# Schematic.net
KiCad netlist of a schematic drawn in EasyEDA
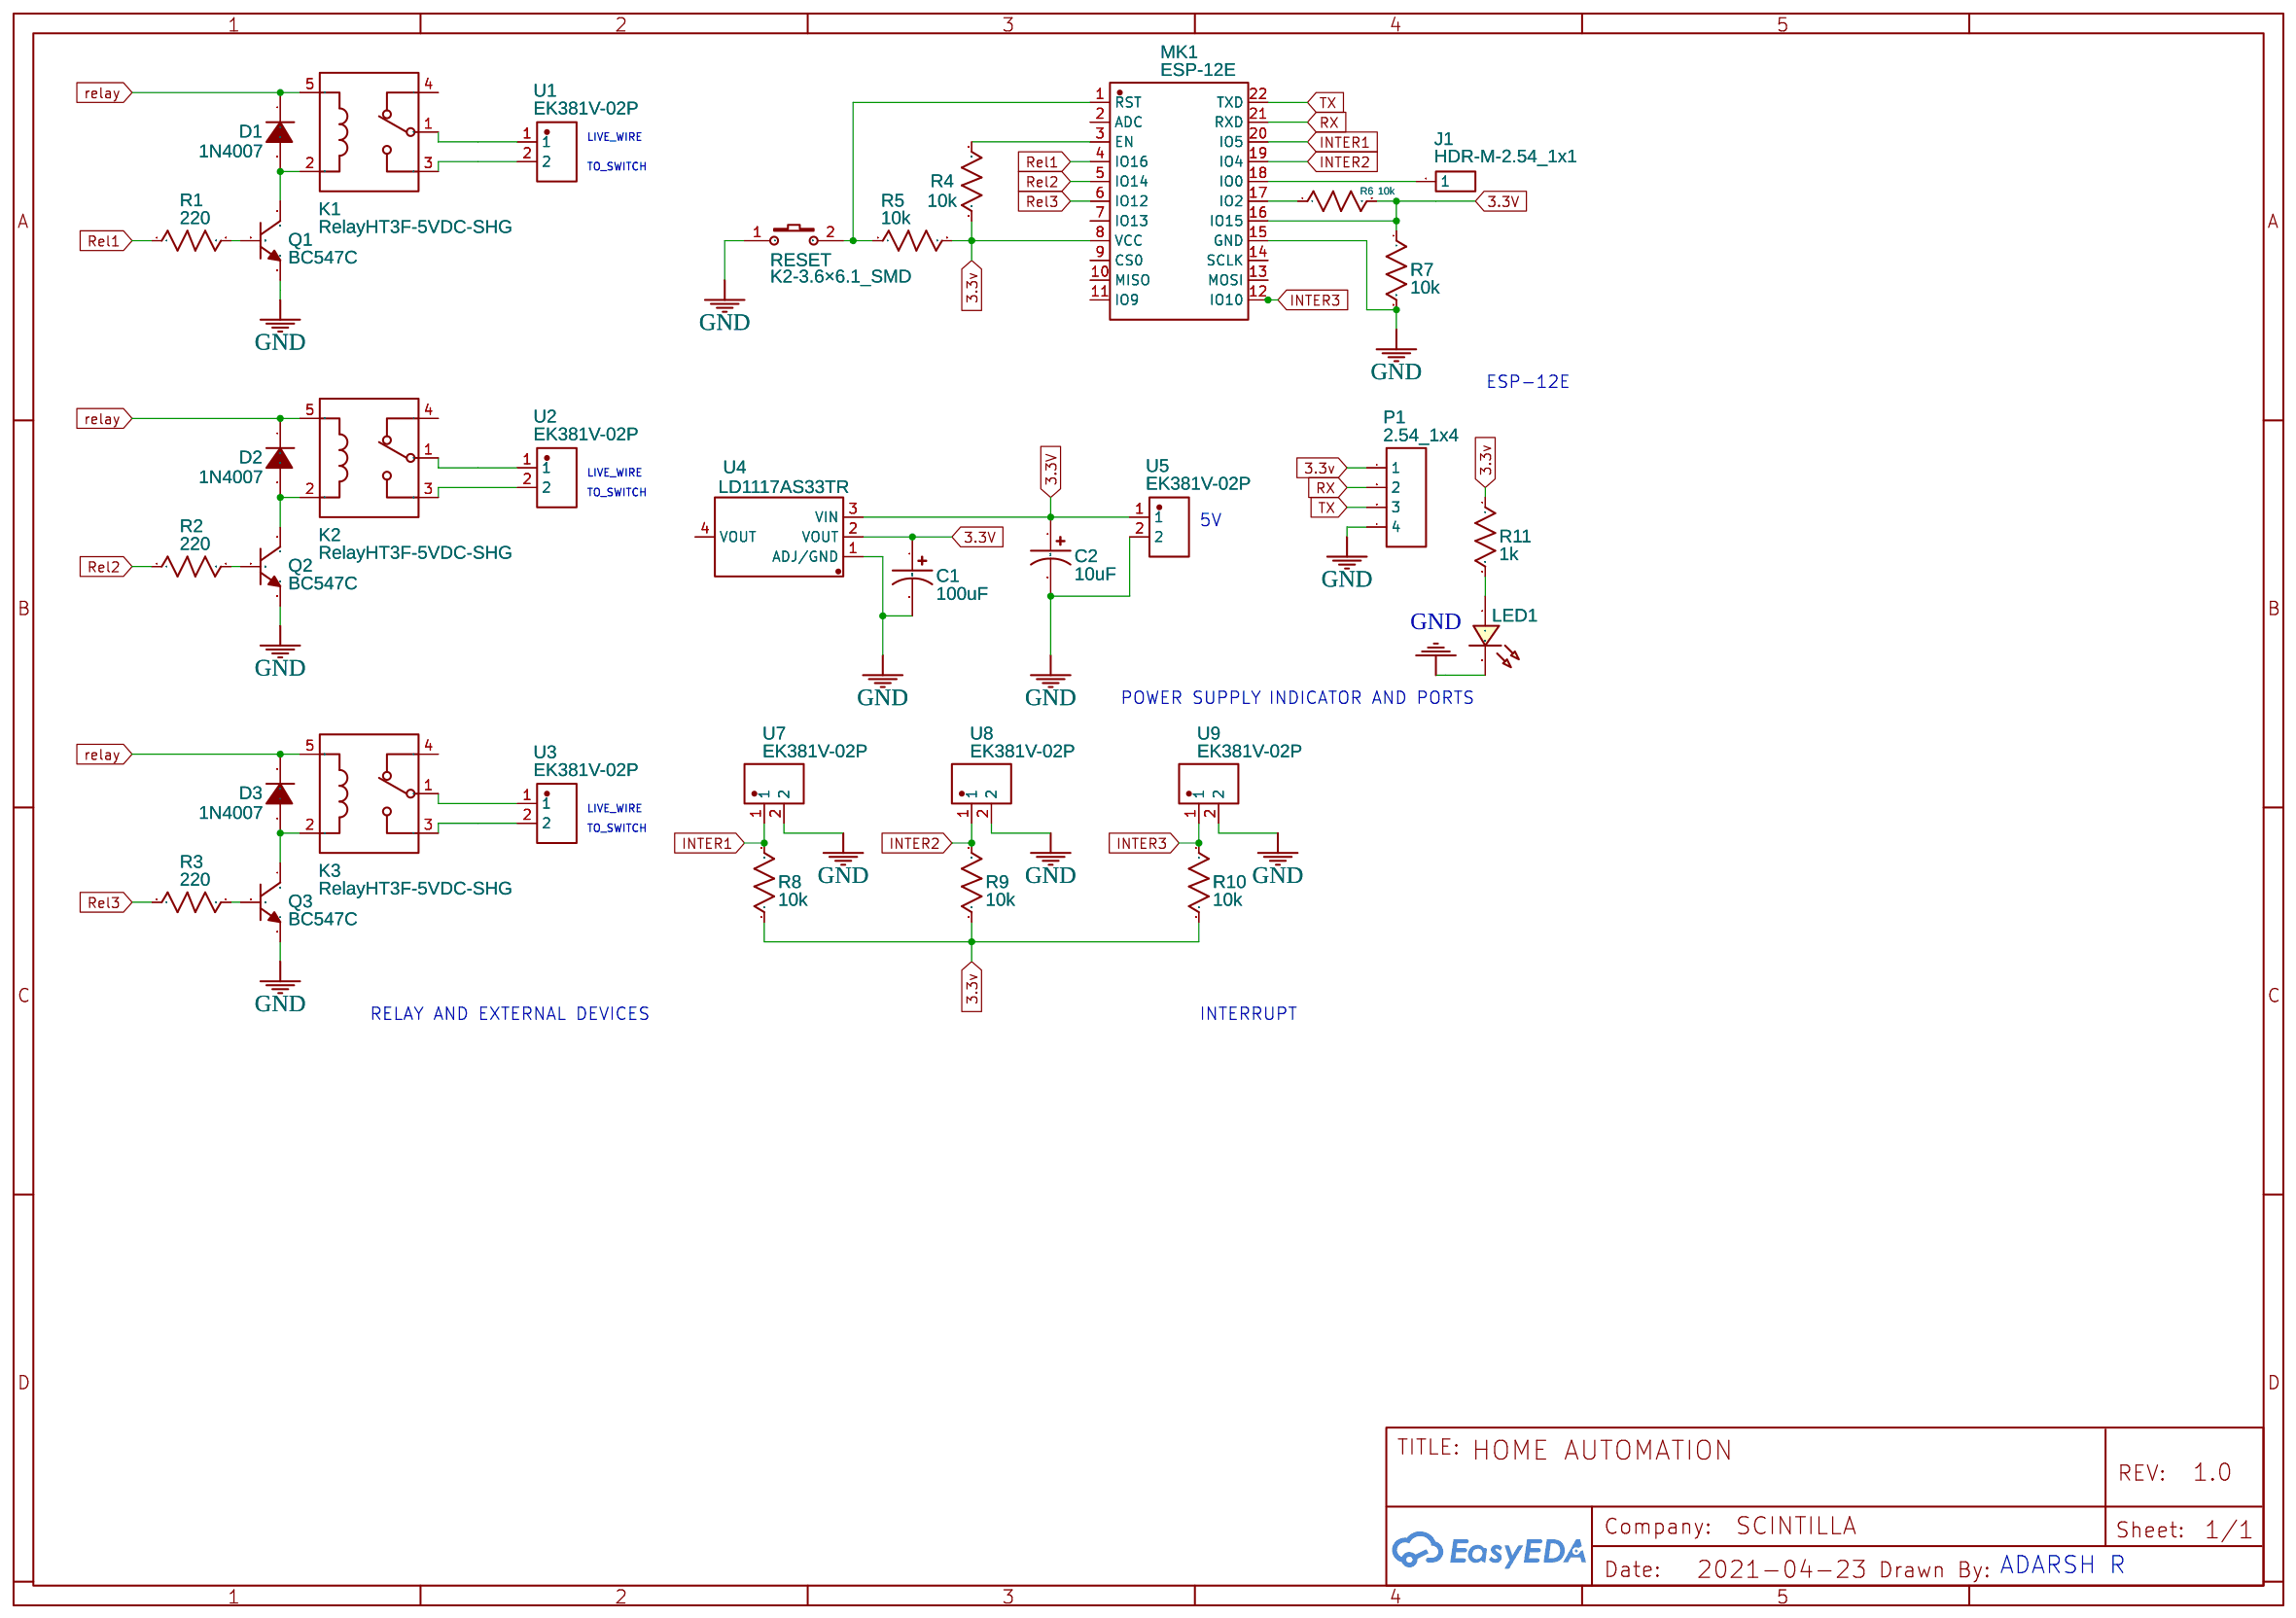
[diagram p0: schematic sheet]

(export (version "E")
  (design (tool "Eeschema 10.0.6"))
  (components
    (comp (ref "C1") (value "100uF") (libsource (lib "") (part "C_Tan_SMD_A_US")))
    (comp (ref "C2") (value "10uF") (libsource (lib "") (part "C_Tan_SMD_A_US")))
    (comp (ref "D1")
      (value "1N4007")
      (fields (field (name "BOM_Supplier Part") "C106903"))
      (libsource (lib "") (part "1N4007"))
    )
    (comp (ref "D2")
      (value "1N4007")
      (fields (field (name "BOM_Supplier Part") "C106903"))
      (libsource (lib "") (part "1N4007"))
    )
    (comp (ref "D3")
      (value "1N4007")
      (fields (field (name "BOM_Supplier Part") "C106903"))
      (libsource (lib "") (part "1N4007"))
    )
    (comp (ref "J1")
      (value "HDR-M-2.54_1x1")
      (fields (field (name "BOM_Supplier Part") "C81276"))
      (libsource (lib "") (part "HDR-M-2.54_1x1"))
    )
    (comp (ref "K1")
      (value "RelayHT3F-5VDC-SHG")
      (fields
        (field (name "BOM_Manufacturer Part") "RelayHT3F-12VDC-SHG")
        (field (name "BOM_Supplier Part") "C22022")
      )
      (libsource (lib "") (part "RelayHT3F-12VDC-SHG"))
    )
    (comp (ref "K2")
      (value "RelayHT3F-5VDC-SHG")
      (fields
        (field (name "BOM_Manufacturer Part") "RelayHT3F-12VDC-SHG")
        (field (name "BOM_Supplier Part") "C22022")
      )
      (libsource (lib "") (part "RelayHT3F-12VDC-SHG"))
    )
    (comp (ref "K3")
      (value "RelayHT3F-5VDC-SHG")
      (fields
        (field (name "BOM_Manufacturer Part") "RelayHT3F-12VDC-SHG")
        (field (name "BOM_Supplier Part") "C22022")
      )
      (libsource (lib "") (part "RelayHT3F-12VDC-SHG"))
    )
    (comp (ref "LED1")
      (value "LED-0603_R")
      (fields
        (field (name "BOM_Manufacturer Part") "19-217/R6C-AL1M2VY/3T")
        (field (name "BOM_Supplier Part") "C72044")
      )
      (libsource (lib "") (part "LED-0603_R"))
    )
    (comp (ref "MK1")
      (value "ESP-12E")
      (fields (field (name "BOM_Supplier Part") "C89297"))
      (libsource (lib "") (part "ESP-12E"))
    )
    (comp (ref "P1")
      (value "2.54_1x4")
      (fields
        (field (name "BOM_Manufacturer Part") "Header-Female-2.54_1x4")
        (field (name "BOM_Supplier Part") "C124413")
      )
      (libsource (lib "") (part "Header-Female-2.54_1x4"))
    )
    (comp (ref "Q1")
      (value "BC547C")
      (fields (field (name "BOM_Supplier Part") "C713614"))
      (libsource (lib "") (part "BC547C"))
    )
    (comp (ref "Q2")
      (value "BC547C")
      (fields (field (name "BOM_Supplier Part") "C713614"))
      (libsource (lib "") (part "BC547C"))
    )
    (comp (ref "Q3")
      (value "BC547C")
      (fields (field (name "BOM_Supplier Part") "C713614"))
      (libsource (lib "") (part "BC547C"))
    )
    (comp (ref "R1") (value "220") (libsource (lib "") (part "R_0603_US_1")))
    (comp (ref "R2") (value "220") (libsource (lib "") (part "R_0603_US_1")))
    (comp (ref "R3") (value "220") (libsource (lib "") (part "R_0603_US_1")))
    (comp (ref "R4") (value "10k") (libsource (lib "") (part "R_0603_US")))
    (comp (ref "R5") (value "10k") (libsource (lib "") (part "R_0603_US_1")))
    (comp (ref "R6") (value "10k") (libsource (lib "") (part "R_0603_US_1")))
    (comp (ref "R7") (value "10k") (libsource (lib "") (part "R_0603_US_2")))
    (comp (ref "R8") (value "10k") (libsource (lib "") (part "R_0603_US")))
    (comp (ref "R9") (value "10k") (libsource (lib "") (part "R_0603_US")))
    (comp (ref "R10") (value "10k") (libsource (lib "") (part "R_0603_US_2")))
    (comp (ref "R11") (value "1k") (libsource (lib "") (part "R_0603_US_2")))
    (comp (ref "RESET")
      (value "K2-3.6×6.1_SMD")
      (fields
        (field (name "BOM_Manufacturer Part") "K2-1107ST-A4SW-06")
        (field (name "BOM_Supplier Part") "C118141")
      )
      (libsource (lib "") (part "K2-3.6×6.1_SMD"))
    )
    (comp (ref "U1")
      (value "EK381V-02P")
      (fields (field (name "BOM_Supplier Part") "C192645"))
      (libsource (lib "") (part "EK381V-02P_1"))
    )
    (comp (ref "U2")
      (value "EK381V-02P")
      (fields (field (name "BOM_Supplier Part") "C192645"))
      (libsource (lib "") (part "EK381V-02P_1"))
    )
    (comp (ref "U3")
      (value "EK381V-02P")
      (fields (field (name "BOM_Supplier Part") "C192645"))
      (libsource (lib "") (part "EK381V-02P_1"))
    )
    (comp (ref "U4")
      (value "LD1117AS33TR")
      (fields (field (name "BOM_Supplier Part") "C115288"))
      (libsource (lib "") (part "LD1117AS33TR"))
    )
    (comp (ref "U5")
      (value "EK381V-02P")
      (fields (field (name "BOM_Supplier Part") "C192645"))
      (libsource (lib "") (part "EK381V-02P_1"))
    )
    (comp (ref "U7")
      (value "EK381V-02P")
      (fields (field (name "BOM_Supplier Part") "C192645"))
      (libsource (lib "") (part "EK381V-02P"))
    )
    (comp (ref "U8")
      (value "EK381V-02P")
      (fields (field (name "BOM_Supplier Part") "C192645"))
      (libsource (lib "") (part "EK381V-02P"))
    )
    (comp (ref "U9")
      (value "EK381V-02P")
      (fields (field (name "BOM_Supplier Part") "C192645"))
      (libsource (lib "") (part "EK381V-02P"))
    )
  )
  (nets
    (net (code "1") (name "3.3V") (class "Default")
      (node (ref "C1") (pin "1") (pinfunction "1_1") (pintype "unspecified"))
      (node (ref "C2") (pin "1") (pinfunction "1_1") (pintype "unspecified"))
      (node (ref "MK1") (pin "16") (pinfunction "IO15_16") (pintype "unspecified"))
      (node (ref "R6") (pin "2") (pinfunction "2_2") (pintype "unspecified"))
      (node (ref "R7") (pin "1") (pinfunction "1_1") (pintype "unspecified"))
      (node (ref "U4") (pin "2") (pinfunction "VOUT_2") (pintype "unspecified"))
      (node (ref "U4") (pin "3") (pinfunction "VIN_3") (pintype "unspecified"))
      (node (ref "U5") (pin "1") (pinfunction "1_1") (pintype "unspecified"))
    )
    (net (code "2") (name "3.3v") (class "Default")
      (node (ref "MK1") (pin "8") (pinfunction "VCC_8") (pintype "unspecified"))
      (node (ref "P1") (pin "1") (pinfunction "1_1") (pintype "input"))
      (node (ref "R10") (pin "2") (pinfunction "2_2") (pintype "unspecified"))
      (node (ref "R11") (pin "1") (pinfunction "1_1") (pintype "unspecified"))
      (node (ref "R4") (pin "1") (pinfunction "1_1") (pintype "unspecified"))
      (node (ref "R5") (pin "2") (pinfunction "2_2") (pintype "unspecified"))
      (node (ref "R8") (pin "1") (pinfunction "1_1") (pintype "unspecified"))
      (node (ref "R9") (pin "1") (pinfunction "1_1") (pintype "unspecified"))
    )
    (net (code "3") (name "GND") (class "Default")
      (node (ref "C1") (pin "2") (pinfunction "2_2") (pintype "unspecified"))
      (node (ref "C2") (pin "2") (pinfunction "2_2") (pintype "unspecified"))
      (node (ref "LED1") (pin "2") (pinfunction "2_2") (pintype "unspecified"))
      (node (ref "MK1") (pin "15") (pinfunction "GND_15") (pintype "unspecified"))
      (node (ref "P1") (pin "4") (pinfunction "4_4") (pintype "input"))
      (node (ref "Q1") (pin "3") (pinfunction "E_3") (pintype "input"))
      (node (ref "Q2") (pin "3") (pinfunction "E_3") (pintype "input"))
      (node (ref "Q3") (pin "3") (pinfunction "E_3") (pintype "input"))
      (node (ref "R7") (pin "2") (pinfunction "2_2") (pintype "unspecified"))
      (node (ref "RESET") (pin "1") (pinfunction "1_1") (pintype "unspecified"))
      (node (ref "U4") (pin "1") (pinfunction "ADJ/GND_1") (pintype "unspecified"))
      (node (ref "U5") (pin "2") (pinfunction "2_2") (pintype "unspecified"))
      (node (ref "U7") (pin "2") (pinfunction "2_2") (pintype "unspecified"))
      (node (ref "U8") (pin "2") (pinfunction "2_2") (pintype "unspecified"))
      (node (ref "U9") (pin "2") (pinfunction "2_2") (pintype "unspecified"))
    )
    (net (code "4") (name "INTER1") (class "Default")
      (node (ref "MK1") (pin "20") (pinfunction "IO5_20") (pintype "unspecified"))
      (node (ref "R8") (pin "2") (pinfunction "2_2") (pintype "unspecified"))
      (node (ref "U7") (pin "1") (pinfunction "1_1") (pintype "unspecified"))
    )
    (net (code "5") (name "INTER2") (class "Default")
      (node (ref "MK1") (pin "19") (pinfunction "IO4_19") (pintype "unspecified"))
      (node (ref "R9") (pin "2") (pinfunction "2_2") (pintype "unspecified"))
      (node (ref "U8") (pin "1") (pinfunction "1_1") (pintype "unspecified"))
    )
    (net (code "6") (name "INTER3") (class "Default")
      (node (ref "MK1") (pin "12") (pinfunction "IO10_12") (pintype "unspecified"))
      (node (ref "R10") (pin "1") (pinfunction "1_1") (pintype "unspecified"))
      (node (ref "U9") (pin "1") (pinfunction "1_1") (pintype "unspecified"))
    )
    (net (code "7") (name "Net-(D1-A)") (class "Default")
      (node (ref "D1") (pin "2") (pinfunction "A_2") (pintype "unspecified"))
      (node (ref "K1") (pin "2") (pinfunction "2_2") (pintype "unspecified"))
      (node (ref "Q1") (pin "1") (pinfunction "C_1") (pintype "input"))
    )
    (net (code "8") (name "Net-(D2-A)") (class "Default")
      (node (ref "D2") (pin "2") (pinfunction "A_2") (pintype "unspecified"))
      (node (ref "K2") (pin "2") (pinfunction "2_2") (pintype "unspecified"))
      (node (ref "Q2") (pin "1") (pinfunction "C_1") (pintype "input"))
    )
    (net (code "9") (name "Net-(D3-A)") (class "Default")
      (node (ref "D3") (pin "2") (pinfunction "A_2") (pintype "unspecified"))
      (node (ref "K3") (pin "2") (pinfunction "2_2") (pintype "unspecified"))
      (node (ref "Q3") (pin "1") (pinfunction "C_1") (pintype "input"))
    )
    (net (code "10") (name "Net-(K1-Pad1)") (class "Default")
      (node (ref "K1") (pin "1") (pinfunction "1_1") (pintype "unspecified"))
      (node (ref "U1") (pin "1") (pinfunction "1_1") (pintype "unspecified"))
    )
    (net (code "11") (name "Net-(K1-Pad3)") (class "Default")
      (node (ref "K1") (pin "3") (pinfunction "3_3") (pintype "unspecified"))
      (node (ref "U1") (pin "2") (pinfunction "2_2") (pintype "unspecified"))
    )
    (net (code "12") (name "Net-(K2-Pad1)") (class "Default")
      (node (ref "K2") (pin "1") (pinfunction "1_1") (pintype "unspecified"))
      (node (ref "U2") (pin "1") (pinfunction "1_1") (pintype "unspecified"))
    )
    (net (code "13") (name "Net-(K2-Pad3)") (class "Default")
      (node (ref "K2") (pin "3") (pinfunction "3_3") (pintype "unspecified"))
      (node (ref "U2") (pin "2") (pinfunction "2_2") (pintype "unspecified"))
    )
    (net (code "14") (name "Net-(K3-Pad1)") (class "Default")
      (node (ref "K3") (pin "1") (pinfunction "1_1") (pintype "unspecified"))
      (node (ref "U3") (pin "1") (pinfunction "1_1") (pintype "unspecified"))
    )
    (net (code "15") (name "Net-(K3-Pad3)") (class "Default")
      (node (ref "K3") (pin "3") (pinfunction "3_3") (pintype "unspecified"))
      (node (ref "U3") (pin "2") (pinfunction "2_2") (pintype "unspecified"))
    )
    (net (code "16") (name "Net-(LED1-Pad1)") (class "Default")
      (node (ref "LED1") (pin "1") (pinfunction "1_1") (pintype "unspecified"))
      (node (ref "R11") (pin "2") (pinfunction "2_2") (pintype "unspecified"))
    )
    (net (code "17") (name "Net-(MK1-EN)") (class "Default")
      (node (ref "MK1") (pin "3") (pinfunction "EN_3") (pintype "unspecified"))
      (node (ref "R4") (pin "2") (pinfunction "2_2") (pintype "unspecified"))
    )
    (net (code "18") (name "Net-(MK1-IO0)") (class "Default")
      (node (ref "J1") (pin "1") (pinfunction "1_1") (pintype "input"))
      (node (ref "MK1") (pin "18") (pinfunction "IO0_18") (pintype "unspecified"))
    )
    (net (code "19") (name "Net-(MK1-IO2)") (class "Default")
      (node (ref "MK1") (pin "17") (pinfunction "IO2_17") (pintype "unspecified"))
      (node (ref "R6") (pin "1") (pinfunction "1_1") (pintype "unspecified"))
    )
    (net (code "20") (name "Net-(MK1-RST)") (class "Default")
      (node (ref "MK1") (pin "1") (pinfunction "RST_1") (pintype "unspecified"))
      (node (ref "R5") (pin "1") (pinfunction "1_1") (pintype "unspecified"))
      (node (ref "RESET") (pin "2") (pinfunction "2_2") (pintype "unspecified"))
    )
    (net (code "21") (name "Net-(Q1-B)") (class "Default")
      (node (ref "Q1") (pin "2") (pinfunction "B_2") (pintype "input"))
      (node (ref "R1") (pin "2") (pinfunction "2_2") (pintype "unspecified"))
    )
    (net (code "22") (name "Net-(Q2-B)") (class "Default")
      (node (ref "Q2") (pin "2") (pinfunction "B_2") (pintype "input"))
      (node (ref "R2") (pin "2") (pinfunction "2_2") (pintype "unspecified"))
    )
    (net (code "23") (name "Net-(Q3-B)") (class "Default")
      (node (ref "Q3") (pin "2") (pinfunction "B_2") (pintype "input"))
      (node (ref "R3") (pin "2") (pinfunction "2_2") (pintype "unspecified"))
    )
    (net (code "24") (name "RX") (class "Default")
      (node (ref "MK1") (pin "21") (pinfunction "RXD_21") (pintype "unspecified"))
      (node (ref "P1") (pin "2") (pinfunction "2_2") (pintype "input"))
    )
    (net (code "25") (name "Rel1") (class "Default")
      (node (ref "MK1") (pin "4") (pinfunction "IO16_4") (pintype "unspecified"))
      (node (ref "R1") (pin "1") (pinfunction "1_1") (pintype "unspecified"))
    )
    (net (code "26") (name "Rel2") (class "Default")
      (node (ref "MK1") (pin "5") (pinfunction "IO14_5") (pintype "unspecified"))
      (node (ref "R2") (pin "1") (pinfunction "1_1") (pintype "unspecified"))
    )
    (net (code "27") (name "Rel3") (class "Default")
      (node (ref "MK1") (pin "6") (pinfunction "IO12_6") (pintype "unspecified"))
      (node (ref "R3") (pin "1") (pinfunction "1_1") (pintype "unspecified"))
    )
    (net (code "28") (name "TX") (class "Default")
      (node (ref "MK1") (pin "22") (pinfunction "TXD_22") (pintype "unspecified"))
      (node (ref "P1") (pin "3") (pinfunction "3_3") (pintype "input"))
    )
    (net (code "29") (name "relay") (class "Default")
      (node (ref "D1") (pin "1") (pinfunction "K_1") (pintype "unspecified"))
      (node (ref "D2") (pin "1") (pinfunction "K_1") (pintype "unspecified"))
      (node (ref "D3") (pin "1") (pinfunction "K_1") (pintype "unspecified"))
      (node (ref "K1") (pin "5") (pinfunction "5_5") (pintype "unspecified"))
      (node (ref "K2") (pin "5") (pinfunction "5_5") (pintype "unspecified"))
      (node (ref "K3") (pin "5") (pinfunction "5_5") (pintype "unspecified"))
    )
    (net (code "30") (name "unconnected-(K1-Pad4)") (class "Default")
      (node (ref "K1") (pin "4") (pinfunction "4_4") (pintype "unspecified"))
    )
    (net (code "31") (name "unconnected-(K2-Pad4)") (class "Default")
      (node (ref "K2") (pin "4") (pinfunction "4_4") (pintype "unspecified"))
    )
    (net (code "32") (name "unconnected-(K3-Pad4)") (class "Default")
      (node (ref "K3") (pin "4") (pinfunction "4_4") (pintype "unspecified"))
    )
    (net (code "33") (name "unconnected-(MK1-ADC-Pad2)") (class "Default")
      (node (ref "MK1") (pin "2") (pinfunction "ADC_2") (pintype "unspecified"))
    )
    (net (code "34") (name "unconnected-(MK1-CS0-Pad9)") (class "Default")
      (node (ref "MK1") (pin "9") (pinfunction "CS0_9") (pintype "unspecified"))
    )
    (net (code "35") (name "unconnected-(MK1-IO9-Pad11)") (class "Default")
      (node (ref "MK1") (pin "11") (pinfunction "IO9_11") (pintype "unspecified"))
    )
    (net (code "36") (name "unconnected-(MK1-IO13-Pad7)") (class "Default")
      (node (ref "MK1") (pin "7") (pinfunction "IO13_7") (pintype "unspecified"))
    )
    (net (code "37") (name "unconnected-(MK1-MISO-Pad10)") (class "Default")
      (node (ref "MK1") (pin "10") (pinfunction "MISO_10") (pintype "unspecified"))
    )
    (net (code "38") (name "unconnected-(MK1-MOSI-Pad13)") (class "Default")
      (node (ref "MK1") (pin "13") (pinfunction "MOSI_13") (pintype "unspecified"))
    )
    (net (code "39") (name "unconnected-(MK1-SCLK-Pad14)") (class "Default")
      (node (ref "MK1") (pin "14") (pinfunction "SCLK_14") (pintype "unspecified"))
    )
    (net (code "40") (name "unconnected-(U4-VOUT-Pad4)") (class "Default")
      (node (ref "U4") (pin "4") (pinfunction "VOUT_4") (pintype "unspecified"))
    )
  )
)
